# design.net
KiCad netlist of a schematic drawn in Altium Designer
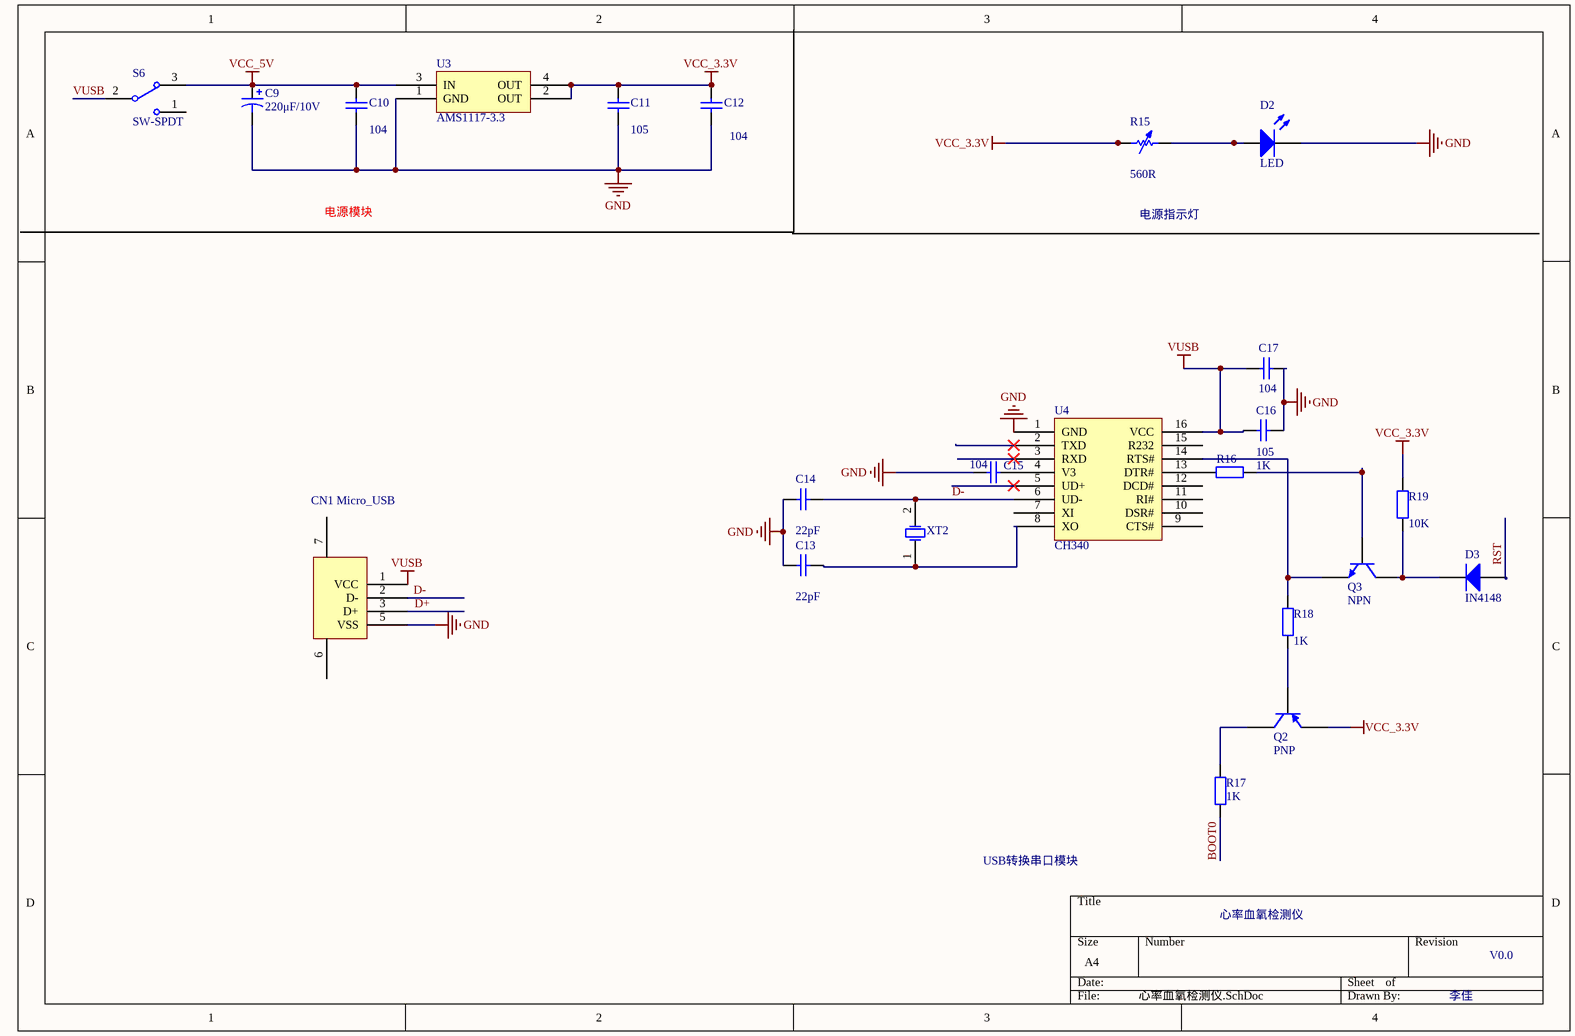
[diagram p0: 心率血氧检测仪.SchDoc]

(export (version "E")
  (design (tool "Eeschema 10.0.6"))
  (components
    (comp (ref "*2")
      (value "CN1 Micro_USB")
      (footprint "SOT-223")
      (libsource (lib "心率血氧") (part "CN1 Micro_USB"))
    )
    (comp (ref "C9")
      (value "220μF/10V")
      (footprint "CAP6.5X6.5")
      (description "Polarized Capacitor (Radial)")
      (fields (field (name "Comment") "Cap Pol1") (field (name "PUBLISHER") "Altium Limited"))
      (libsource (lib "Miscellaneous Devices") (part "Cap Pol1"))
    )
    (comp (ref "C10")
      (value "104")
      (footprint "0805C")
      (description "Capacitor")
      (fields (field (name "Comment") "Cap") (field (name "PUBLISHER") "Altium Limited"))
      (libsource (lib "Miscellaneous Devices") (part "Cap"))
    )
    (comp (ref "C11")
      (value "105")
      (footprint "0805C")
      (description "Capacitor")
      (fields (field (name "Comment") "Cap") (field (name "PUBLISHER") "Altium Limited"))
      (libsource (lib "Miscellaneous Devices") (part "Cap"))
    )
    (comp (ref "C12")
      (value "104")
      (footprint "0805C")
      (description "Capacitor")
      (fields (field (name "Comment") "Cap") (field (name "PUBLISHER") "Altium Limited"))
      (libsource (lib "Miscellaneous Devices") (part "Cap"))
    )
    (comp (ref "C13")
      (value "22pF")
      (footprint "0805C")
      (description "Capacitor")
      (fields (field (name "Comment") "Cap") (field (name "PUBLISHER") "Altium Limited"))
      (libsource (lib "Miscellaneous Devices") (part "Cap"))
    )
    (comp (ref "C14")
      (value "22pF")
      (footprint "0805C")
      (description "Capacitor")
      (fields (field (name "Comment") "Cap") (field (name "PUBLISHER") "Altium Limited"))
      (libsource (lib "Miscellaneous Devices") (part "Cap"))
    )
    (comp (ref "C15")
      (value "104")
      (footprint "0805C")
      (description "Capacitor")
      (fields (field (name "Comment") "Cap") (field (name "PUBLISHER") "Altium Limited"))
      (libsource (lib "Miscellaneous Devices") (part "Cap"))
    )
    (comp (ref "C16")
      (value "105")
      (footprint "0805C")
      (description "Capacitor")
      (fields (field (name "PUBLISHER") "Altium Limited"))
      (libsource (lib "Miscellaneous Devices") (part "Cap"))
    )
    (comp (ref "C17")
      (value "104")
      (footprint "0805C")
      (description "Capacitor")
      (fields (field (name "Comment") "Cap") (field (name "PUBLISHER") "Altium Limited"))
      (libsource (lib "Miscellaneous Devices") (part "Cap"))
    )
    (comp (ref "D2")
      (value "LED")
      (footprint "LED_0805")
      (description "Typical INFRARED GaAs LED")
      (fields (field (name "PUBLISHER") "Altium Limited"))
      (libsource (lib "Miscellaneous Devices") (part "LED0"))
    )
    (comp (ref "D3")
      (value "IN4148")
      (footprint "DO-213AA")
      (description "Default Diode")
      (fields (field (name "PUBLISHER") "Altium Limited"))
      (libsource (lib "Miscellaneous Devices") (part "Diode"))
    )
    (comp (ref "Q2")
      (value "PNP")
      (footprint "SOT-23")
      (description "PNP General Purpose Amplifier")
      (fields (field (name "PUBLISHER") "Altium Limited"))
      (libsource (lib "Miscellaneous Devices") (part "2N3906"))
    )
    (comp (ref "Q3")
      (value "NPN")
      (footprint "SOT-23")
      (description "NPN General Purpose Amplifier")
      (fields (field (name "PUBLISHER") "Altium Limited"))
      (libsource (lib "Miscellaneous Devices") (part "2N3904"))
    )
    (comp (ref "R15")
      (value "560R")
      (footprint "0805")
      (description "Variable Resistor")
      (fields (field (name "Comment") "Res Adj1") (field (name "PUBLISHER") "Altium Limited"))
      (libsource (lib "Miscellaneous Devices") (part "Res Adj1"))
    )
    (comp (ref "R16")
      (value "1K")
      (footprint "0805")
      (description "Resistor")
      (fields (field (name "Comment") "Res2") (field (name "PUBLISHER") "Altium Limited"))
      (libsource (lib "") (part "Res2_1"))
    )
    (comp (ref "R17")
      (value "1K")
      (footprint "0805")
      (description "Resistor")
      (fields (field (name "Comment") "Res2") (field (name "PUBLISHER") "Altium Limited"))
      (libsource (lib "Miscellaneous Devices") (part "Res2"))
    )
    (comp (ref "R18")
      (value "1K")
      (footprint "0805")
      (description "Resistor")
      (fields (field (name "Comment") "Res2") (field (name "PUBLISHER") "Altium Limited"))
      (libsource (lib "Miscellaneous Devices") (part "Res2"))
    )
    (comp (ref "R19")
      (value "10K")
      (footprint "0805")
      (description "Resistor")
      (fields (field (name "Comment") "Res2") (field (name "PUBLISHER") "Altium Limited"))
      (libsource (lib "Miscellaneous Devices") (part "Res2"))
    )
    (comp (ref "S6")
      (value "SW-SPDT")
      (footprint "BTN8*8")
      (description "SPDT Subminiature Toggle Switch, Right Angle Mounting, Vertical Actuation")
      (fields (field (name "PUBLISHER") "Altium Limited"))
      (libsource (lib "Miscellaneous Devices") (part "SW-SPDT"))
    )
    (comp (ref "U3")
      (value "AMS1117-3.3")
      (footprint "SOT-223")
      (libsource (lib "心率血氧") (part "AMS1117-3.3"))
    )
    (comp (ref "U4") (value "CH340") (footprint "SOP16") (libsource (lib "心率血氧") (part "CH340")))
    (comp (ref "XT2")
      (value "XTAL")
      (footprint "HC-49S")
      (description "Crystal Oscillator")
      (fields (field (name "PUBLISHER") "Altium Limited"))
      (libsource (lib "Miscellaneous Devices") (part "XTAL"))
    )
  )
  (nets
    (net (code "1") (name "/BOOT0") (class "Default")
      (node (ref "R17") (pin "1") (pinfunction "1_1") (pintype "passive"))
    )
    (net (code "2") (name "/D+") (class "Default")
      (node (ref "*2") (pin "3") (pinfunction "D+_3") (pintype "passive"))
    )
    (net (code "3") (name "/D-") (class "Default")
      (node (ref "*2") (pin "2") (pinfunction "D-_2") (pintype "passive"))
      (node (ref "C14") (pin "2") (pinfunction "2_2") (pintype "passive"))
      (node (ref "U4") (pin "6") (pinfunction "UD-_6") (pintype "passive"))
      (node (ref "XT2") (pin "2") (pinfunction "OSC2_2") (pintype "passive"))
    )
    (net (code "4") (name "/RST") (class "Default")
      (node (ref "D3") (pin "1") (pinfunction "A_1") (pintype "passive"))
    )
    (net (code "5") (name "GND") (class "Default")
      (node (ref "*2") (pin "5") (pinfunction "VSS_5") (pintype "passive"))
      (node (ref "C10") (pin "2") (pinfunction "2_2") (pintype "passive"))
      (node (ref "C11") (pin "2") (pinfunction "2_2") (pintype "passive"))
      (node (ref "C12") (pin "2") (pinfunction "2_2") (pintype "passive"))
      (node (ref "C13") (pin "1") (pinfunction "1_1") (pintype "passive"))
      (node (ref "C14") (pin "1") (pinfunction "1_1") (pintype "passive"))
      (node (ref "C15") (pin "1") (pinfunction "1_1") (pintype "passive"))
      (node (ref "C16") (pin "2") (pinfunction "2_2") (pintype "passive"))
      (node (ref "C17") (pin "2") (pinfunction "2_2") (pintype "passive"))
      (node (ref "C9") (pin "2") (pinfunction "2_2") (pintype "passive"))
      (node (ref "D2") (pin "2") (pinfunction "K_2") (pintype "passive"))
      (node (ref "U3") (pin "1") (pinfunction "GND_1") (pintype "passive"))
      (node (ref "U4") (pin "1") (pinfunction "GND_1") (pintype "passive"))
    )
    (net (code "6") (name "Net-(D2-A)") (class "Default")
      (node (ref "D2") (pin "1") (pinfunction "A_1") (pintype "passive"))
      (node (ref "R15") (pin "2") (pinfunction "2_2") (pintype "passive"))
    )
    (net (code "7") (name "Net-(D3-K)") (class "Default")
      (node (ref "D3") (pin "2") (pinfunction "K_2") (pintype "passive"))
      (node (ref "Q3") (pin "3") (pinfunction "C_3") (pintype "passive"))
      (node (ref "R19") (pin "1") (pinfunction "1_1") (pintype "passive"))
    )
    (net (code "8") (name "Net-(Q2-B)") (class "Default")
      (node (ref "Q2") (pin "2") (pinfunction "B_2") (pintype "passive"))
      (node (ref "R18") (pin "1") (pinfunction "1_1") (pintype "passive"))
    )
    (net (code "9") (name "Net-(Q2-C)") (class "Default")
      (node (ref "Q2") (pin "3") (pinfunction "C_3") (pintype "passive"))
      (node (ref "R17") (pin "2") (pinfunction "2_2") (pintype "passive"))
    )
    (net (code "10") (name "Net-(Q3-B)") (class "Default")
      (node (ref "Q3") (pin "2") (pinfunction "B_2") (pintype "passive"))
      (node (ref "R16") (pin "2") (pinfunction "2_2") (pintype "passive"))
    )
    (net (code "11") (name "Net-(Q3-E)") (class "Default")
      (node (ref "Q3") (pin "1") (pinfunction "E_1") (pintype "passive"))
      (node (ref "R18") (pin "2") (pinfunction "2_2") (pintype "passive"))
      (node (ref "U4") (pin "14") (pinfunction "RTS#_14") (pintype "passive"))
    )
    (net (code "12") (name "Net-(U4-DTR#)") (class "Default")
      (node (ref "R16") (pin "1") (pinfunction "1_1") (pintype "passive"))
      (node (ref "U4") (pin "13") (pinfunction "DTR#_13") (pintype "passive"))
    )
    (net (code "13") (name "Net-(U4-V3)") (class "Default")
      (node (ref "C15") (pin "2") (pinfunction "2_2") (pintype "passive"))
      (node (ref "U4") (pin "4") (pinfunction "V3_4") (pintype "passive"))
    )
    (net (code "14") (name "Net-(U4-XO)") (class "Default")
      (node (ref "C13") (pin "2") (pinfunction "2_2") (pintype "passive"))
      (node (ref "U4") (pin "8") (pinfunction "XO_8") (pintype "passive"))
      (node (ref "XT2") (pin "1") (pinfunction "OSC1_1") (pintype "passive"))
    )
    (net (code "15") (name "VCC_3.3V") (class "Default")
      (node (ref "C11") (pin "1") (pinfunction "1_1") (pintype "passive"))
      (node (ref "C12") (pin "1") (pinfunction "1_1") (pintype "passive"))
      (node (ref "Q2") (pin "1") (pinfunction "E_1") (pintype "passive"))
      (node (ref "R15") (pin "1") (pinfunction "1_1") (pintype "passive"))
      (node (ref "R19") (pin "2") (pinfunction "2_2") (pintype "passive"))
      (node (ref "U3") (pin "2") (pinfunction "OUT_2") (pintype "passive"))
      (node (ref "U3") (pin "4") (pinfunction "OUT_4") (pintype "passive"))
    )
    (net (code "16") (name "VCC_5V") (class "Default")
      (node (ref "C10") (pin "1") (pinfunction "1_1") (pintype "passive"))
      (node (ref "C9") (pin "1") (pinfunction "1_1") (pintype "passive"))
      (node (ref "S6") (pin "3") (pinfunction "3_3") (pintype "passive"))
      (node (ref "U3") (pin "3") (pinfunction "IN_3") (pintype "passive"))
    )
    (net (code "17") (name "VUSB") (class "Default")
      (node (ref "*2") (pin "1") (pinfunction "VCC_1") (pintype "passive"))
      (node (ref "C16") (pin "1") (pinfunction "1_1") (pintype "passive"))
      (node (ref "C17") (pin "1") (pinfunction "1_1") (pintype "passive"))
      (node (ref "S6") (pin "2") (pinfunction "2_2") (pintype "passive"))
      (node (ref "U4") (pin "16") (pinfunction "VCC_16") (pintype "passive"))
    )
    (net (code "18") (name "unconnected-(*2-6-Pad7)") (class "Default")
      (node (ref "*2") (pin "7") (pinfunction "6_7") (pintype "passive"))
    )
    (net (code "19") (name "unconnected-(*2-7-Pad6)") (class "Default")
      (node (ref "*2") (pin "6") (pinfunction "7_6") (pintype "passive"))
    )
    (net (code "20") (name "unconnected-(S6-Pad1)") (class "Default")
      (node (ref "S6") (pin "1") (pinfunction "1_1") (pintype "passive"))
    )
    (net (code "21") (name "unconnected-(U4-CTS#-Pad9)") (class "Default")
      (node (ref "U4") (pin "9") (pinfunction "CTS#_9") (pintype "passive"))
    )
    (net (code "22") (name "unconnected-(U4-DCD#-Pad12)") (class "Default")
      (node (ref "U4") (pin "12") (pinfunction "DCD#_12") (pintype "passive"))
    )
    (net (code "23") (name "unconnected-(U4-DSR#-Pad10)") (class "Default")
      (node (ref "U4") (pin "10") (pinfunction "DSR#_10") (pintype "passive"))
    )
    (net (code "24") (name "unconnected-(U4-R232-Pad15)") (class "Default")
      (node (ref "U4") (pin "15") (pinfunction "R232_15") (pintype "passive"))
    )
    (net (code "25") (name "unconnected-(U4-RI#-Pad11)") (class "Default")
      (node (ref "U4") (pin "11") (pinfunction "RI#_11") (pintype "passive"))
    )
    (net (code "26") (name "unconnected-(U4-RXD-Pad3)") (class "Default")
      (node (ref "U4") (pin "3") (pinfunction "RXD_3") (pintype "passive+no_connect"))
    )
    (net (code "27") (name "unconnected-(U4-TXD-Pad2)") (class "Default")
      (node (ref "U4") (pin "2") (pinfunction "TXD_2") (pintype "passive+no_connect"))
    )
    (net (code "28") (name "unconnected-(U4-UD+-Pad5)") (class "Default")
      (node (ref "U4") (pin "5") (pinfunction "UD+_5") (pintype "passive+no_connect"))
    )
    (net (code "29") (name "unconnected-(U4-XI-Pad7)") (class "Default")
      (node (ref "U4") (pin "7") (pinfunction "XI_7") (pintype "passive"))
    )
  )
)
